# sensors.net
KiCad netlist of a schematic drawn in Altium Designer
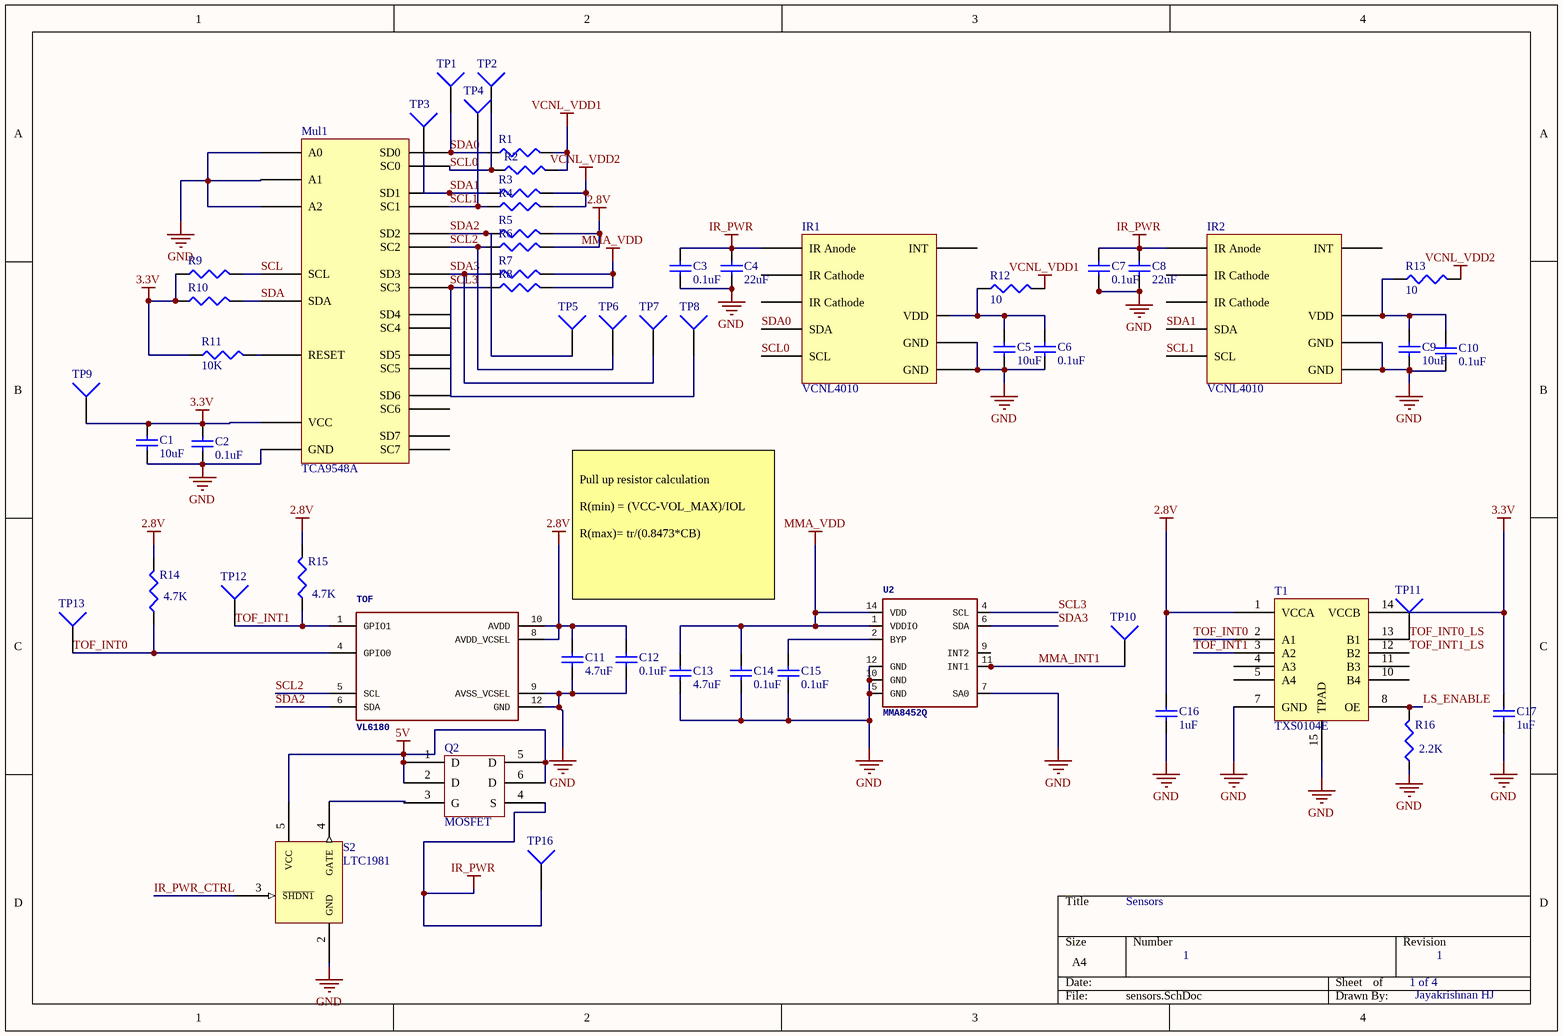
[diagram p0: sensors.SchDoc]

(export (version "E")
  (design (tool "Eeschema 10.0.6"))
  (components
    (comp (ref "C1")
      (value "10uF")
      (footprint "1608[0603]")
      (description "CAP CER 10UF 10V X5R 0603")
      (fields
        (field (name "DIGIKEY PART NO") "490-10474-1-ND")
        (field (name "MANUFACTURER") "Murata Electronics North America")
      )
      (libsource (lib "Miscellaneous Devices") (part "Cap Semi"))
    )
    (comp (ref "C2")
      (value "0.1uF")
      (footprint "1608[0603]")
      (description "CAP CER 0.1UF 10V X7R 0603")
      (fields (field (name "DIGIKEY PART NO") "399-1095-1-ND") (field (name "MANUFACTURER") "KEMET"))
      (libsource (lib "Miscellaneous Devices") (part "Cap Semi"))
    )
    (comp (ref "C3")
      (value "0.1uF")
      (footprint "1608[0603]")
      (description "CAP CER 0.1UF 10V X7R 0603")
      (fields (field (name "DIGIKEY PART NO") "399-1095-1-ND") (field (name "MANUFACTURER") "KEMET"))
      (libsource (lib "Miscellaneous Devices") (part "Cap Semi"))
    )
    (comp (ref "C4")
      (value "22uF")
      (footprint "1608[0603]")
      (description "CAP CER 22UF 6.3V X5R 0603")
      (fields
        (field (name "DIGIKEY PART NO") "490-7611-1-ND")
        (field (name "MANUFACTURER") "Murata Electronics North America")
      )
      (libsource (lib "Miscellaneous Devices") (part "Cap Semi"))
    )
    (comp (ref "C5")
      (value "10uF")
      (footprint "1608[0603]")
      (description "CAP CER 10UF 10V X5R 0603")
      (fields
        (field (name "DIGIKEY PART NO") "490-10474-1-ND")
        (field (name "MANUFACTURER") "Murata Electronics North America")
      )
      (libsource (lib "Miscellaneous Devices") (part "Cap Semi"))
    )
    (comp (ref "C6")
      (value "0.1uF")
      (footprint "1608[0603]")
      (description "CAP CER 0.1UF 10V X7R 0603")
      (fields (field (name "DIGIKEY PART NO") "399-1095-1-ND") (field (name "MANUFACTURER") "KEMET"))
      (libsource (lib "Miscellaneous Devices") (part "Cap Semi"))
    )
    (comp (ref "C7")
      (value "0.1uF")
      (footprint "1608[0603]")
      (description "CAP CER 0.1UF 10V X7R 0603")
      (fields (field (name "DIGIKEY PART NO") "399-1095-1-ND") (field (name "MANUFACTURER") "KEMET"))
      (libsource (lib "Miscellaneous Devices") (part "Cap Semi"))
    )
    (comp (ref "C8")
      (value "22uF")
      (footprint "1608[0603]")
      (description "CAP CER 22UF 6.3V X5R 0603")
      (fields
        (field (name "DIGIKEY PART NO") "490-7611-1-ND")
        (field (name "MANUFACTURER") "Murata Electronics North America")
      )
      (libsource (lib "Miscellaneous Devices") (part "Cap Semi"))
    )
    (comp (ref "C9")
      (value "10uF")
      (footprint "1608[0603]")
      (description "CAP CER 10UF 10V X5R 0603")
      (fields
        (field (name "DIGIKEY PART NO") "490-10474-1-ND")
        (field (name "MANUFACTURER") "Murata Electronics North America")
      )
      (libsource (lib "Miscellaneous Devices") (part "Cap Semi"))
    )
    (comp (ref "C10")
      (value "0.1uF")
      (footprint "1608[0603]")
      (description "CAP CER 0.1UF 10V X7R 0603")
      (fields (field (name "DIGIKEY PART NO") "399-1095-1-ND") (field (name "MANUFACTURER") "KEMET"))
      (libsource (lib "Miscellaneous Devices") (part "Cap Semi"))
    )
    (comp (ref "C11")
      (value "4.7uF")
      (footprint "1608[0603]")
      (description "CAP CER 4.7UF 10V X5R 0603")
      (fields
        (field (name "DIGIKEY PART NO") "490-10477-1-ND")
        (field (name "MANUFACTURER") "Murata Electronics North America")
      )
      (libsource (lib "Miscellaneous Devices") (part "Cap Semi"))
    )
    (comp (ref "C12")
      (value "0.1uF")
      (footprint "1608[0603]")
      (description "CAP CER 0.1UF 10V X7R 0603")
      (fields (field (name "DIGIKEY PART NO") "399-1095-1-ND") (field (name "MANUFACTURER") "KEMET"))
      (libsource (lib "Miscellaneous Devices") (part "Cap Semi"))
    )
    (comp (ref "C13")
      (value "4.7uF")
      (footprint "1608[0603]")
      (description "CAP CER 4.7UF 10V X5R 0603")
      (fields
        (field (name "DIGIKEY PART NO") "490-10477-1-ND")
        (field (name "MANUFACTURER") "Murata Electronics North America")
      )
      (libsource (lib "Miscellaneous Devices") (part "Cap Semi"))
    )
    (comp (ref "C14")
      (value "0.1uF")
      (footprint "1608[0603]")
      (description "CAP CER 0.1UF 10V X7R 0603")
      (fields (field (name "DIGIKEY PART NO") "399-1095-1-ND") (field (name "MANUFACTURER") "KEMET"))
      (libsource (lib "Miscellaneous Devices") (part "Cap Semi"))
    )
    (comp (ref "C15")
      (value "0.1uF")
      (footprint "1608[0603]")
      (description "CAP CER 0.1UF 10V X7R 0603")
      (fields (field (name "DIGIKEY PART NO") "399-1095-1-ND") (field (name "MANUFACTURER") "KEMET"))
      (libsource (lib "Miscellaneous Devices") (part "Cap Semi"))
    )
    (comp (ref "C16")
      (value "1uF")
      (footprint "1608[0603]")
      (description "CAP CER 1UF 10V X7R 0603")
      (fields
        (field (name "DIGIKEY PART NO") "1276-1946-1-ND")
        (field (name "MANUFACTURER") "Samsung Electro-Mechanics America, Inc.")
      )
      (libsource (lib "Miscellaneous Devices") (part "Cap Semi"))
    )
    (comp (ref "C17")
      (value "1uF")
      (footprint "1608[0603]")
      (description "CAP CER 1UF 10V X7R 0603")
      (fields
        (field (name "DIGIKEY PART NO") "1276-1946-1-ND")
        (field (name "MANUFACTURER") "Samsung Electro-Mechanics America, Inc.")
      )
      (libsource (lib "Miscellaneous Devices") (part "Cap Semi"))
    )
    (comp (ref "IR1")
      (value "VCNL4010")
      (footprint "13-WQFN")
      (description "SENS IR PROXIMITY AMB LT 12LLP")
      (fields
        (field (name "MANUFACTURER") "Vishay Semiconductor Opto Division")
        (field (name "MANUFACTURER PART NUMBER") "VCNL4010-GS08")
      )
      (libsource (lib "SensorFingerComponents") (part "VCNL4010"))
    )
    (comp (ref "IR2")
      (value "VCNL4010")
      (footprint "13-WQFN")
      (description "SENS IR PROXIMITY AMB LT 12LLP")
      (fields
        (field (name "MANUFACTURER PART NUMBER") "VCNL4010-GS08")
        (field (name "DIGIKEY PART NO") "VCNL4010-GS08CT-ND")
      )
      (libsource (lib "SensorFingerComponents") (part "VCNL4010"))
    )
    (comp (ref "Mul1")
      (value "TCA9548A")
      (footprint "TTSOP MULTIPLEXER")
      (description "IC I2C SW 8CH W/RESET 24TSSOP")
      (fields
        (field (name "DIGIKEY PART NUMBER") "296-34905-1-ND")
        (field (name "MANUFACTURER") "Texas Instruments")
      )
      (libsource (lib "SensorFingerComponents") (part "TCA9548A"))
    )
    (comp (ref "Q2")
      (value "MOSFET")
      (footprint "MOSFET SI3442")
      (description "MOSFET N-CH 20V 3A 6-TSOP")
      (fields
        (field (name "DIGIKEY PART NO") "SI3442BDV-T1-E3CT-ND")
        (field (name "MANUFACTURER PART NUMBER") "SI3442BDV-T1-E3")
      )
      (libsource (lib "parts") (part "MOSFET"))
    )
    (comp (ref "R1")
      (value "Res3")
      (footprint "J1-0603")
      (description "RES SMD 4.7K OHM 5% 1/10W 0603")
      (fields (field (name "DIGIKEY PART NO") "311-4.7KGRCT-ND") (field (name "MANUFACTURER") "Yageo"))
      (libsource (lib "Miscellaneous Devices") (part "Res3"))
    )
    (comp (ref "R2")
      (value "Res3")
      (footprint "J1-0603")
      (description "RES SMD 4.7K OHM 5% 1/10W 0603")
      (fields (field (name "DIGIKEY PART NO") "311-4.7KGRCT-ND") (field (name "MANUFACTURER") "Yageo"))
      (libsource (lib "Miscellaneous Devices") (part "Res3"))
    )
    (comp (ref "R3")
      (value "Res3")
      (footprint "J1-0603")
      (description "RES SMD 4.7K OHM 5% 1/10W 0603")
      (fields (field (name "DIGIKEY PART NO") "311-4.7KGRCT-ND") (field (name "MANUFACTURER") "Yageo"))
      (libsource (lib "Miscellaneous Devices") (part "Res3"))
    )
    (comp (ref "R4")
      (value "Res3")
      (footprint "J1-0603")
      (description "RES SMD 4.7K OHM 5% 1/10W 0603")
      (fields (field (name "DIGIKEY PART NO") "311-4.7KGRCT-ND") (field (name "MANUFACTURER") "Yageo"))
      (libsource (lib "Miscellaneous Devices") (part "Res3"))
    )
    (comp (ref "R5")
      (value "Res3")
      (footprint "J1-0603")
      (description "RES SMD 4.7K OHM 5% 1/10W 0603")
      (fields (field (name "DIGIKEY PART NO") "311-4.7KGRCT-ND") (field (name "MANUFACTURER") "Yageo"))
      (libsource (lib "Miscellaneous Devices") (part "Res3"))
    )
    (comp (ref "R6")
      (value "Res3")
      (footprint "J1-0603")
      (description "RES SMD 4.7K OHM 5% 1/10W 0603")
      (fields (field (name "DIGIKEY PART NO") "311-4.7KGRCT-ND") (field (name "MANUFACTURER") "Yageo"))
      (libsource (lib "Miscellaneous Devices") (part "Res3"))
    )
    (comp (ref "R7")
      (value "Res3")
      (footprint "J1-0603")
      (description "RES SMD 4.7K OHM 5% 1/10W 0603")
      (fields (field (name "DIGIKEY PART NO") "311-4.7KGRCT-ND") (field (name "MANUFACTURER") "Yageo"))
      (libsource (lib "Miscellaneous Devices") (part "Res3"))
    )
    (comp (ref "R8")
      (value "Res3")
      (footprint "J1-0603")
      (description "RES SMD 4.7K OHM 5% 1/10W 0603")
      (fields (field (name "DIGIKEY PART NO") "311-4.7KGRCT-ND") (field (name "MANUFACTURER") "Yageo"))
      (libsource (lib "Miscellaneous Devices") (part "Res3"))
    )
    (comp (ref "R9")
      (value "Res3")
      (footprint "J1-0603")
      (description "RES SMD 4.7K OHM 5% 1/10W 0603")
      (fields (field (name "DIGIKEY PART NO") "311-4.7KGRCT-ND") (field (name "MANUFACTURER") "Yageo"))
      (libsource (lib "Miscellaneous Devices") (part "Res3"))
    )
    (comp (ref "R10")
      (value "Res3")
      (footprint "J1-0603")
      (description "RES SMD 4.7K OHM 5% 1/10W 0603")
      (fields (field (name "DIGIKEY PART NO") "311-4.7KGRCT-ND") (field (name "MANUFACTURER") "Yageo"))
      (libsource (lib "Miscellaneous Devices") (part "Res3"))
    )
    (comp (ref "R11")
      (value "10K")
      (footprint "J1-0603")
      (description "RES SMD 10K OHM 5% 1/16W 0402")
      (fields (field (name "DIGIKEY PART NO") "311-10KJRCT-ND") (field (name "MANUFACTURER") "Yageo"))
      (libsource (lib "Miscellaneous Devices") (part "Res3"))
    )
    (comp (ref "R12")
      (value "10")
      (footprint "J1-0603")
      (description "RES SMD 10 OHM 1% 1/10W 0603")
      (fields (field (name "DIGIKEY PART NO") "311-10.0HRCT-ND") (field (name "MANUFACTURER") "Yageo"))
      (libsource (lib "Miscellaneous Devices") (part "Res3"))
    )
    (comp (ref "R13")
      (value "10")
      (footprint "J1-0603")
      (description "RES SMD 10 OHM 1% 1/10W 0603")
      (fields (field (name "DIGIKEY PART NO") "311-10.0HRCT-ND") (field (name "MANUFACTURER") "Yageo"))
      (libsource (lib "Miscellaneous Devices") (part "Res3"))
    )
    (comp (ref "R14")
      (value "4.7K")
      (footprint "1608[0603]")
      (description "RES SMD 4.7K OHM 5% 1/10W 0603")
      (fields (field (name "DIGIKEY PART NO") "311-4.7KGRCT-ND") (field (name "MANUFACTURER") "Yageo"))
      (libsource (lib "Miscellaneous Devices") (part "Res3"))
    )
    (comp (ref "R15")
      (value "4.7K")
      (footprint "1608[0603]")
      (description "RES SMD 4.7K OHM 5% 1/10W 0603")
      (fields (field (name "DIGIKEY PART NO") "311-4.7KGRCT-ND") (field (name "MANUFACTURER") "Yageo"))
      (libsource (lib "Miscellaneous Devices") (part "Res3"))
    )
    (comp (ref "R16")
      (value "2.2K")
      (footprint "J1-0603")
      (description "RES SMD 2.2K OHM 1% 1/16W 0402")
      (fields (field (name "DIGIKEY PART NO") "311-2.20KLRCT-ND") (field (name "MANUFACTURER") "Yageo"))
      (libsource (lib "Miscellaneous Devices") (part "Res3"))
    )
    (comp (ref "S2")
      (value "LTC1981")
      (footprint "LTC1981")
      (description "IC HI-SIDE SW CTRL SNGL TSOT23-5")
      (fields
        (field (name "MANUFACTURER PART NUMBER") "LTC1981ES5#TRMPBF")
        (field (name "DIGIKEY PART NO") "LTC1981ES5#TRMPBFCT-ND")
      )
      (libsource (lib "Parts") (part "LTC1981"))
    )
    (comp (ref "T1")
      (value "TXS0104E")
      (footprint "txs0104e")
      (description "IC 4BIT NON-INV TRANSLTR 14-QFN")
      (fields
        (field (name "DIGIKEY PART NO") "296-20698-1-ND")
        (field (name "MANUFACTURER PART NUMBER") "TXS0104ERGYR")
      )
      (libsource (lib "Robonauts_parts") (part "TXS0104E"))
    )
    (comp (ref "TOF")
      (value "VL6180")
      (footprint "VL6180")
      (description "MOD TIME-OF-FLIGHT 3IN1 12LGA")
      (fields
        (field (name "DIGIKEY PART NO") "497-14702-1-ND")
        (field (name "MANUFACTURER") "STMicroelectronics")
      )
      (libsource (lib "Correll_sensor_parts") (part "VL6180"))
    )
    (comp (ref "TP1")
      (value "Socket")
      (footprint "PIN1")
      (fields (field (name "PUBLISHER") "Altium Limited"))
      (libsource (lib "Miscellaneous Connectors") (part "Socket"))
    )
    (comp (ref "TP2")
      (value "Socket")
      (footprint "PIN1")
      (fields (field (name "PUBLISHER") "Altium Limited"))
      (libsource (lib "Miscellaneous Connectors") (part "Socket"))
    )
    (comp (ref "TP3")
      (value "Socket")
      (footprint "PIN1")
      (fields (field (name "PUBLISHER") "Altium Limited"))
      (libsource (lib "Miscellaneous Connectors") (part "Socket"))
    )
    (comp (ref "TP4")
      (value "Socket")
      (footprint "PIN1")
      (fields (field (name "PUBLISHER") "Altium Limited"))
      (libsource (lib "Miscellaneous Connectors") (part "Socket"))
    )
    (comp (ref "TP5")
      (value "Socket")
      (footprint "PIN1")
      (fields (field (name "PUBLISHER") "Altium Limited"))
      (libsource (lib "Miscellaneous Connectors") (part "Socket"))
    )
    (comp (ref "TP6")
      (value "Socket")
      (footprint "PIN1")
      (fields (field (name "PUBLISHER") "Altium Limited"))
      (libsource (lib "Miscellaneous Connectors") (part "Socket"))
    )
    (comp (ref "TP7")
      (value "Socket")
      (footprint "PIN1")
      (fields (field (name "PUBLISHER") "Altium Limited"))
      (libsource (lib "Miscellaneous Connectors") (part "Socket"))
    )
    (comp (ref "TP8")
      (value "Socket")
      (footprint "PIN1")
      (fields (field (name "PUBLISHER") "Altium Limited"))
      (libsource (lib "Miscellaneous Connectors") (part "Socket"))
    )
    (comp (ref "TP9")
      (value "Socket")
      (footprint "PIN1")
      (fields (field (name "PUBLISHER") "Altium Limited"))
      (libsource (lib "Miscellaneous Connectors") (part "Socket"))
    )
    (comp (ref "TP10")
      (value "Socket")
      (footprint "PIN1")
      (fields (field (name "PUBLISHER") "Altium Limited"))
      (libsource (lib "Miscellaneous Connectors") (part "Socket"))
    )
    (comp (ref "TP11")
      (value "Socket")
      (footprint "PIN1")
      (fields (field (name "PUBLISHER") "Altium Limited"))
      (libsource (lib "Miscellaneous Connectors") (part "Socket"))
    )
    (comp (ref "TP12")
      (value "Socket")
      (footprint "PIN1")
      (fields (field (name "PUBLISHER") "Altium Limited"))
      (libsource (lib "Miscellaneous Connectors") (part "Socket"))
    )
    (comp (ref "TP13")
      (value "Socket")
      (footprint "PIN1")
      (fields (field (name "PUBLISHER") "Altium Limited"))
      (libsource (lib "Miscellaneous Connectors") (part "Socket"))
    )
    (comp (ref "TP16")
      (value "Socket")
      (footprint "PIN1")
      (fields (field (name "PUBLISHER") "Altium Limited"))
      (libsource (lib "Miscellaneous Connectors") (part "Socket"))
    )
    (comp (ref "U2")
      (value "MMA8452Q")
      (footprint "MMA8452Q_jk")
      (description "ACCELEROMETER 2-8G I2C 16QFN")
      (fields (field (name "DIGIKEY PART NO") "MMA8452QR1CT-ND") (field (name "MANUFACTURER") "NXP USA Inc."))
      (libsource (lib "Robonauts_parts") (part "MMA8452Q"))
    )
  )
  (nets
    (net (code "1") (name "/IR_PWR_CTRL") (class "Default")
      (node (ref "S2") (pin "3") (pinfunction "~{SHDN1}_3") (pintype "input"))
    )
    (net (code "2") (name "/LS_ENABLE") (class "Default")
      (node (ref "R16") (pin "2") (pinfunction "2_2") (pintype "passive"))
      (node (ref "T1") (pin "8") (pinfunction "OE_8") (pintype "passive"))
    )
    (net (code "3") (name "/MMA_INT1") (class "Default")
      (node (ref "TP10") (pin "1") (pinfunction "1_1") (pintype "passive"))
      (node (ref "U2") (pin "11") (pinfunction "INT1_11") (pintype "passive"))
    )
    (net (code "4") (name "/SCL") (class "Default")
      (node (ref "Mul1") (pin "22") (pinfunction "SCL_22") (pintype "passive"))
      (node (ref "R9") (pin "2") (pinfunction "2_2") (pintype "passive"))
    )
    (net (code "5") (name "/SCL0") (class "Default")
      (node (ref "IR1") (pin "5") (pinfunction "SCL_5") (pintype "passive"))
      (node (ref "Mul1") (pin "5") (pinfunction "SC0_5") (pintype "passive"))
      (node (ref "R2") (pin "1") (pinfunction "1_1") (pintype "passive"))
      (node (ref "TP2") (pin "1") (pinfunction "1_1") (pintype "passive"))
    )
    (net (code "6") (name "/SCL1") (class "Default")
      (node (ref "IR2") (pin "5") (pinfunction "SCL_5") (pintype "passive"))
      (node (ref "Mul1") (pin "7") (pinfunction "SC1_7") (pintype "passive"))
      (node (ref "R4") (pin "1") (pinfunction "1_1") (pintype "passive"))
      (node (ref "TP4") (pin "1") (pinfunction "1_1") (pintype "passive"))
    )
    (net (code "7") (name "/SCL2") (class "Default")
      (node (ref "Mul1") (pin "9") (pinfunction "SC2_9") (pintype "passive"))
      (node (ref "R6") (pin "1") (pinfunction "1_1") (pintype "passive"))
      (node (ref "TOF") (pin "5") (pinfunction "SCL_5") (pintype "passive"))
      (node (ref "TP6") (pin "1") (pinfunction "1_1") (pintype "passive"))
    )
    (net (code "8") (name "/SCL3") (class "Default")
      (node (ref "Mul1") (pin "11") (pinfunction "SC3_11") (pintype "passive"))
      (node (ref "R8") (pin "1") (pinfunction "1_1") (pintype "passive"))
      (node (ref "TP8") (pin "1") (pinfunction "1_1") (pintype "passive"))
      (node (ref "U2") (pin "4") (pinfunction "SCL_4") (pintype "passive"))
    )
    (net (code "9") (name "/SDA") (class "Default")
      (node (ref "Mul1") (pin "23") (pinfunction "SDA_23") (pintype "passive"))
      (node (ref "R10") (pin "2") (pinfunction "2_2") (pintype "passive"))
    )
    (net (code "10") (name "/SDA0") (class "Default")
      (node (ref "IR1") (pin "4") (pinfunction "SDA_4") (pintype "passive"))
      (node (ref "Mul1") (pin "4") (pinfunction "SD0_4") (pintype "passive"))
      (node (ref "R1") (pin "1") (pinfunction "1_1") (pintype "passive"))
      (node (ref "TP1") (pin "1") (pinfunction "1_1") (pintype "passive"))
    )
    (net (code "11") (name "/SDA1") (class "Default")
      (node (ref "IR2") (pin "4") (pinfunction "SDA_4") (pintype "passive"))
      (node (ref "Mul1") (pin "6") (pinfunction "SD1_6") (pintype "passive"))
      (node (ref "R3") (pin "1") (pinfunction "1_1") (pintype "passive"))
      (node (ref "TP3") (pin "1") (pinfunction "1_1") (pintype "passive"))
    )
    (net (code "12") (name "/SDA2") (class "Default")
      (node (ref "Mul1") (pin "8") (pinfunction "SD2_8") (pintype "passive"))
      (node (ref "R5") (pin "1") (pinfunction "1_1") (pintype "passive"))
      (node (ref "TOF") (pin "6") (pinfunction "SDA_6") (pintype "passive"))
      (node (ref "TP5") (pin "1") (pinfunction "1_1") (pintype "passive"))
    )
    (net (code "13") (name "/SDA3") (class "Default")
      (node (ref "Mul1") (pin "10") (pinfunction "SD3_10") (pintype "passive"))
      (node (ref "R7") (pin "1") (pinfunction "1_1") (pintype "passive"))
      (node (ref "TP7") (pin "1") (pinfunction "1_1") (pintype "passive"))
      (node (ref "U2") (pin "6") (pinfunction "SDA_6") (pintype "passive"))
    )
    (net (code "14") (name "/TOF_INT0") (class "Default")
      (node (ref "R14") (pin "1") (pinfunction "1_1") (pintype "passive"))
      (node (ref "T1") (pin "2") (pinfunction "A1_2") (pintype "passive"))
      (node (ref "TOF") (pin "4") (pinfunction "GPIO0_4") (pintype "passive"))
      (node (ref "TP13") (pin "1") (pinfunction "1_1") (pintype "passive"))
    )
    (net (code "15") (name "/TOF_INT0_LS") (class "Default")
      (node (ref "T1") (pin "13") (pinfunction "B1_13") (pintype "passive"))
      (node (ref "TP11") (pin "1") (pinfunction "1_1") (pintype "passive"))
    )
    (net (code "16") (name "/TOF_INT1") (class "Default")
      (node (ref "R15") (pin "1") (pinfunction "1_1") (pintype "passive"))
      (node (ref "T1") (pin "3") (pinfunction "A2_3") (pintype "passive"))
      (node (ref "TOF") (pin "1") (pinfunction "GPIO1_1") (pintype "passive"))
      (node (ref "TP12") (pin "1") (pinfunction "1_1") (pintype "passive"))
    )
    (net (code "17") (name "/TOF_INT1_LS") (class "Default")
      (node (ref "T1") (pin "12") (pinfunction "B2_12") (pintype "passive"))
    )
    (net (code "18") (name "2.8V") (class "Default")
      (node (ref "C11") (pin "2") (pinfunction "2_2") (pintype "passive"))
      (node (ref "C12") (pin "2") (pinfunction "2_2") (pintype "passive"))
      (node (ref "C16") (pin "2") (pinfunction "2_2") (pintype "passive"))
      (node (ref "R14") (pin "2") (pinfunction "2_2") (pintype "passive"))
      (node (ref "R15") (pin "2") (pinfunction "2_2") (pintype "passive"))
      (node (ref "R5") (pin "2") (pinfunction "2_2") (pintype "passive"))
      (node (ref "R6") (pin "2") (pinfunction "2_2") (pintype "passive"))
      (node (ref "T1") (pin "1") (pinfunction "VCCA_1") (pintype "passive"))
      (node (ref "TOF") (pin "10") (pinfunction "AVDD_10") (pintype "passive"))
      (node (ref "TOF") (pin "8") (pinfunction "AVDD_VCSEL_8") (pintype "passive"))
    )
    (net (code "19") (name "3.3V") (class "Default")
      (node (ref "C1") (pin "2") (pinfunction "2_2") (pintype "passive"))
      (node (ref "C17") (pin "2") (pinfunction "2_2") (pintype "passive"))
      (node (ref "C2") (pin "2") (pinfunction "2_2") (pintype "passive"))
      (node (ref "Mul1") (pin "24") (pinfunction "VCC_24") (pintype "passive"))
      (node (ref "R10") (pin "1") (pinfunction "1_1") (pintype "passive"))
      (node (ref "R11") (pin "1") (pinfunction "1_1") (pintype "passive"))
      (node (ref "R9") (pin "1") (pinfunction "1_1") (pintype "passive"))
      (node (ref "T1") (pin "14") (pinfunction "VCCB_14") (pintype "passive"))
      (node (ref "TP9") (pin "1") (pinfunction "1_1") (pintype "passive"))
    )
    (net (code "20") (name "5V") (class "Default")
      (node (ref "Q2") (pin "1") (pinfunction "D_1") (pintype "passive"))
      (node (ref "Q2") (pin "2") (pinfunction "D_2") (pintype "passive"))
      (node (ref "Q2") (pin "5") (pinfunction "D_5") (pintype "passive"))
      (node (ref "Q2") (pin "6") (pinfunction "D_6") (pintype "passive"))
      (node (ref "S2") (pin "5") (pinfunction "VCC_5") (pintype "power_in"))
    )
    (net (code "21") (name "GND") (class "Default")
      (node (ref "C1") (pin "1") (pinfunction "1_1") (pintype "passive"))
      (node (ref "C10") (pin "1") (pinfunction "1_1") (pintype "passive"))
      (node (ref "C11") (pin "1") (pinfunction "1_1") (pintype "passive"))
      (node (ref "C12") (pin "1") (pinfunction "1_1") (pintype "passive"))
      (node (ref "C13") (pin "1") (pinfunction "1_1") (pintype "passive"))
      (node (ref "C14") (pin "1") (pinfunction "1_1") (pintype "passive"))
      (node (ref "C15") (pin "1") (pinfunction "1_1") (pintype "passive"))
      (node (ref "C16") (pin "1") (pinfunction "1_1") (pintype "passive"))
      (node (ref "C17") (pin "1") (pinfunction "1_1") (pintype "passive"))
      (node (ref "C2") (pin "1") (pinfunction "1_1") (pintype "passive"))
      (node (ref "C3") (pin "1") (pinfunction "1_1") (pintype "passive"))
      (node (ref "C4") (pin "1") (pinfunction "1_1") (pintype "passive"))
      (node (ref "C5") (pin "1") (pinfunction "1_1") (pintype "passive"))
      (node (ref "C6") (pin "1") (pinfunction "1_1") (pintype "passive"))
      (node (ref "C7") (pin "1") (pinfunction "1_1") (pintype "passive"))
      (node (ref "C8") (pin "1") (pinfunction "1_1") (pintype "passive"))
      (node (ref "C9") (pin "1") (pinfunction "1_1") (pintype "passive"))
      (node (ref "IR1") (pin "12") (pinfunction "GND_12") (pintype "passive"))
      (node (ref "IR1") (pin "13") (pinfunction "GND_13") (pintype "passive"))
      (node (ref "IR2") (pin "12") (pinfunction "GND_12") (pintype "passive"))
      (node (ref "IR2") (pin "13") (pinfunction "GND_13") (pintype "passive"))
      (node (ref "Mul1") (pin "1") (pinfunction "A0_1") (pintype "passive"))
      (node (ref "Mul1") (pin "12") (pinfunction "GND_12") (pintype "passive"))
      (node (ref "Mul1") (pin "2") (pinfunction "A1_2") (pintype "passive"))
      (node (ref "Mul1") (pin "21") (pinfunction "A2_21") (pintype "passive"))
      (node (ref "R16") (pin "1") (pinfunction "1_1") (pintype "passive"))
      (node (ref "S2") (pin "2") (pinfunction "GND_2") (pintype "power_in"))
      (node (ref "T1") (pin "15") (pinfunction "TPAD_15") (pintype "power_in"))
      (node (ref "T1") (pin "7") (pinfunction "GND_7") (pintype "passive"))
      (node (ref "TOF") (pin "12") (pinfunction "GND_12") (pintype "passive"))
      (node (ref "TOF") (pin "9") (pinfunction "AVSS_VCSEL_9") (pintype "passive"))
      (node (ref "U2") (pin "10") (pinfunction "GND_10") (pintype "passive"))
      (node (ref "U2") (pin "12") (pinfunction "GND_12") (pintype "passive"))
      (node (ref "U2") (pin "5") (pinfunction "GND_5") (pintype "passive"))
      (node (ref "U2") (pin "7") (pinfunction "SA0_7") (pintype "passive"))
    )
    (net (code "22") (name "IR_PWR") (class "Default")
      (node (ref "C3") (pin "2") (pinfunction "2_2") (pintype "passive"))
      (node (ref "C4") (pin "2") (pinfunction "2_2") (pintype "passive"))
      (node (ref "C7") (pin "2") (pinfunction "2_2") (pintype "passive"))
      (node (ref "C8") (pin "2") (pinfunction "2_2") (pintype "passive"))
      (node (ref "IR1") (pin "1") (pinfunction "IR_Anode_1") (pintype "passive"))
      (node (ref "IR2") (pin "1") (pinfunction "IR_Anode_1") (pintype "passive"))
      (node (ref "Q2") (pin "4") (pinfunction "S_4") (pintype "passive"))
      (node (ref "TP16") (pin "1") (pinfunction "1_1") (pintype "passive"))
    )
    (net (code "23") (name "MMA_VDD") (class "Default")
      (node (ref "C13") (pin "2") (pinfunction "2_2") (pintype "passive"))
      (node (ref "C14") (pin "2") (pinfunction "2_2") (pintype "passive"))
      (node (ref "R7") (pin "2") (pinfunction "2_2") (pintype "passive"))
      (node (ref "R8") (pin "2") (pinfunction "2_2") (pintype "passive"))
      (node (ref "U2") (pin "1") (pinfunction "VDDIO_1") (pintype "passive"))
      (node (ref "U2") (pin "14") (pinfunction "VDD_14") (pintype "passive"))
    )
    (net (code "24") (name "Net-(IR1-VDD)") (class "Default")
      (node (ref "C5") (pin "2") (pinfunction "2_2") (pintype "passive"))
      (node (ref "C6") (pin "2") (pinfunction "2_2") (pintype "passive"))
      (node (ref "IR1") (pin "7") (pinfunction "VDD_7") (pintype "passive"))
      (node (ref "R12") (pin "1") (pinfunction "1_1") (pintype "passive"))
    )
    (net (code "25") (name "Net-(IR2-VDD)") (class "Default")
      (node (ref "C10") (pin "2") (pinfunction "2_2") (pintype "passive"))
      (node (ref "C9") (pin "2") (pinfunction "2_2") (pintype "passive"))
      (node (ref "IR2") (pin "7") (pinfunction "VDD_7") (pintype "passive"))
      (node (ref "R13") (pin "1") (pinfunction "1_1") (pintype "passive"))
    )
    (net (code "26") (name "Net-(Mul1-RESET)") (class "Default")
      (node (ref "Mul1") (pin "3") (pinfunction "RESET_3") (pintype "passive"))
      (node (ref "R11") (pin "2") (pinfunction "2_2") (pintype "passive"))
    )
    (net (code "27") (name "Net-(Q2-G)") (class "Default")
      (node (ref "Q2") (pin "3") (pinfunction "G_3") (pintype "passive"))
      (node (ref "S2") (pin "4") (pinfunction "GATE_4") (pintype "output"))
    )
    (net (code "28") (name "Net-(U2-BYP)") (class "Default")
      (node (ref "C15") (pin "2") (pinfunction "2_2") (pintype "passive"))
      (node (ref "U2") (pin "2") (pinfunction "BYP_2") (pintype "passive"))
    )
    (net (code "29") (name "VCNL_VDD1") (class "Default")
      (node (ref "R1") (pin "2") (pinfunction "2_2") (pintype "passive"))
      (node (ref "R12") (pin "2") (pinfunction "2_2") (pintype "passive"))
      (node (ref "R2") (pin "2") (pinfunction "2_2") (pintype "passive"))
    )
    (net (code "30") (name "VCNL_VDD2") (class "Default")
      (node (ref "R13") (pin "2") (pinfunction "2_2") (pintype "passive"))
      (node (ref "R3") (pin "2") (pinfunction "2_2") (pintype "passive"))
      (node (ref "R4") (pin "2") (pinfunction "2_2") (pintype "passive"))
    )
    (net (code "31") (name "unconnected-(IR1-INT-Pad6)") (class "Default")
      (node (ref "IR1") (pin "6") (pinfunction "INT_6") (pintype "passive"))
    )
    (net (code "32") (name "unconnected-(IR1-IR_Cathode-Pad2)") (class "Default")
      (node (ref "IR1") (pin "2") (pinfunction "IR_Cathode_2") (pintype "passive"))
    )
    (net (code "33") (name "unconnected-(IR1-IR_Cathode-Pad3)") (class "Default")
      (node (ref "IR1") (pin "3") (pinfunction "IR_Cathode_3") (pintype "passive"))
    )
    (net (code "34") (name "unconnected-(IR2-INT-Pad6)") (class "Default")
      (node (ref "IR2") (pin "6") (pinfunction "INT_6") (pintype "passive"))
    )
    (net (code "35") (name "unconnected-(IR2-IR_Cathode-Pad2)") (class "Default")
      (node (ref "IR2") (pin "2") (pinfunction "IR_Cathode_2") (pintype "passive"))
    )
    (net (code "36") (name "unconnected-(IR2-IR_Cathode-Pad3)") (class "Default")
      (node (ref "IR2") (pin "3") (pinfunction "IR_Cathode_3") (pintype "passive"))
    )
    (net (code "37") (name "unconnected-(Mul1-SC4-Pad14)") (class "Default")
      (node (ref "Mul1") (pin "14") (pinfunction "SC4_14") (pintype "passive"))
    )
    (net (code "38") (name "unconnected-(Mul1-SC5-Pad16)") (class "Default")
      (node (ref "Mul1") (pin "16") (pinfunction "SC5_16") (pintype "passive"))
    )
    (net (code "39") (name "unconnected-(Mul1-SC6-Pad18)") (class "Default")
      (node (ref "Mul1") (pin "18") (pinfunction "SC6_18") (pintype "passive"))
    )
    (net (code "40") (name "unconnected-(Mul1-SC7-Pad20)") (class "Default")
      (node (ref "Mul1") (pin "20") (pinfunction "SC7_20") (pintype "passive"))
    )
    (net (code "41") (name "unconnected-(Mul1-SD4-Pad13)") (class "Default")
      (node (ref "Mul1") (pin "13") (pinfunction "SD4_13") (pintype "passive"))
    )
    (net (code "42") (name "unconnected-(Mul1-SD5-Pad15)") (class "Default")
      (node (ref "Mul1") (pin "15") (pinfunction "SD5_15") (pintype "passive"))
    )
    (net (code "43") (name "unconnected-(Mul1-SD6-Pad17)") (class "Default")
      (node (ref "Mul1") (pin "17") (pinfunction "SD6_17") (pintype "passive"))
    )
    (net (code "44") (name "unconnected-(Mul1-SD7-Pad19)") (class "Default")
      (node (ref "Mul1") (pin "19") (pinfunction "SD7_19") (pintype "passive"))
    )
    (net (code "45") (name "unconnected-(T1-A3-Pad4)") (class "Default")
      (node (ref "T1") (pin "4") (pinfunction "A3_4") (pintype "passive"))
    )
    (net (code "46") (name "unconnected-(T1-A4-Pad5)") (class "Default")
      (node (ref "T1") (pin "5") (pinfunction "A4_5") (pintype "passive"))
    )
    (net (code "47") (name "unconnected-(T1-B3-Pad11)") (class "Default")
      (node (ref "T1") (pin "11") (pinfunction "B3_11") (pintype "passive"))
    )
    (net (code "48") (name "unconnected-(T1-B4-Pad10)") (class "Default")
      (node (ref "T1") (pin "10") (pinfunction "B4_10") (pintype "passive"))
    )
    (net (code "49") (name "unconnected-(U2-INT2-Pad9)") (class "Default")
      (node (ref "U2") (pin "9") (pinfunction "INT2_9") (pintype "passive"))
    )
  )
)
